# M715.net
KiCad netlist of a schematic drawn in EAGLE
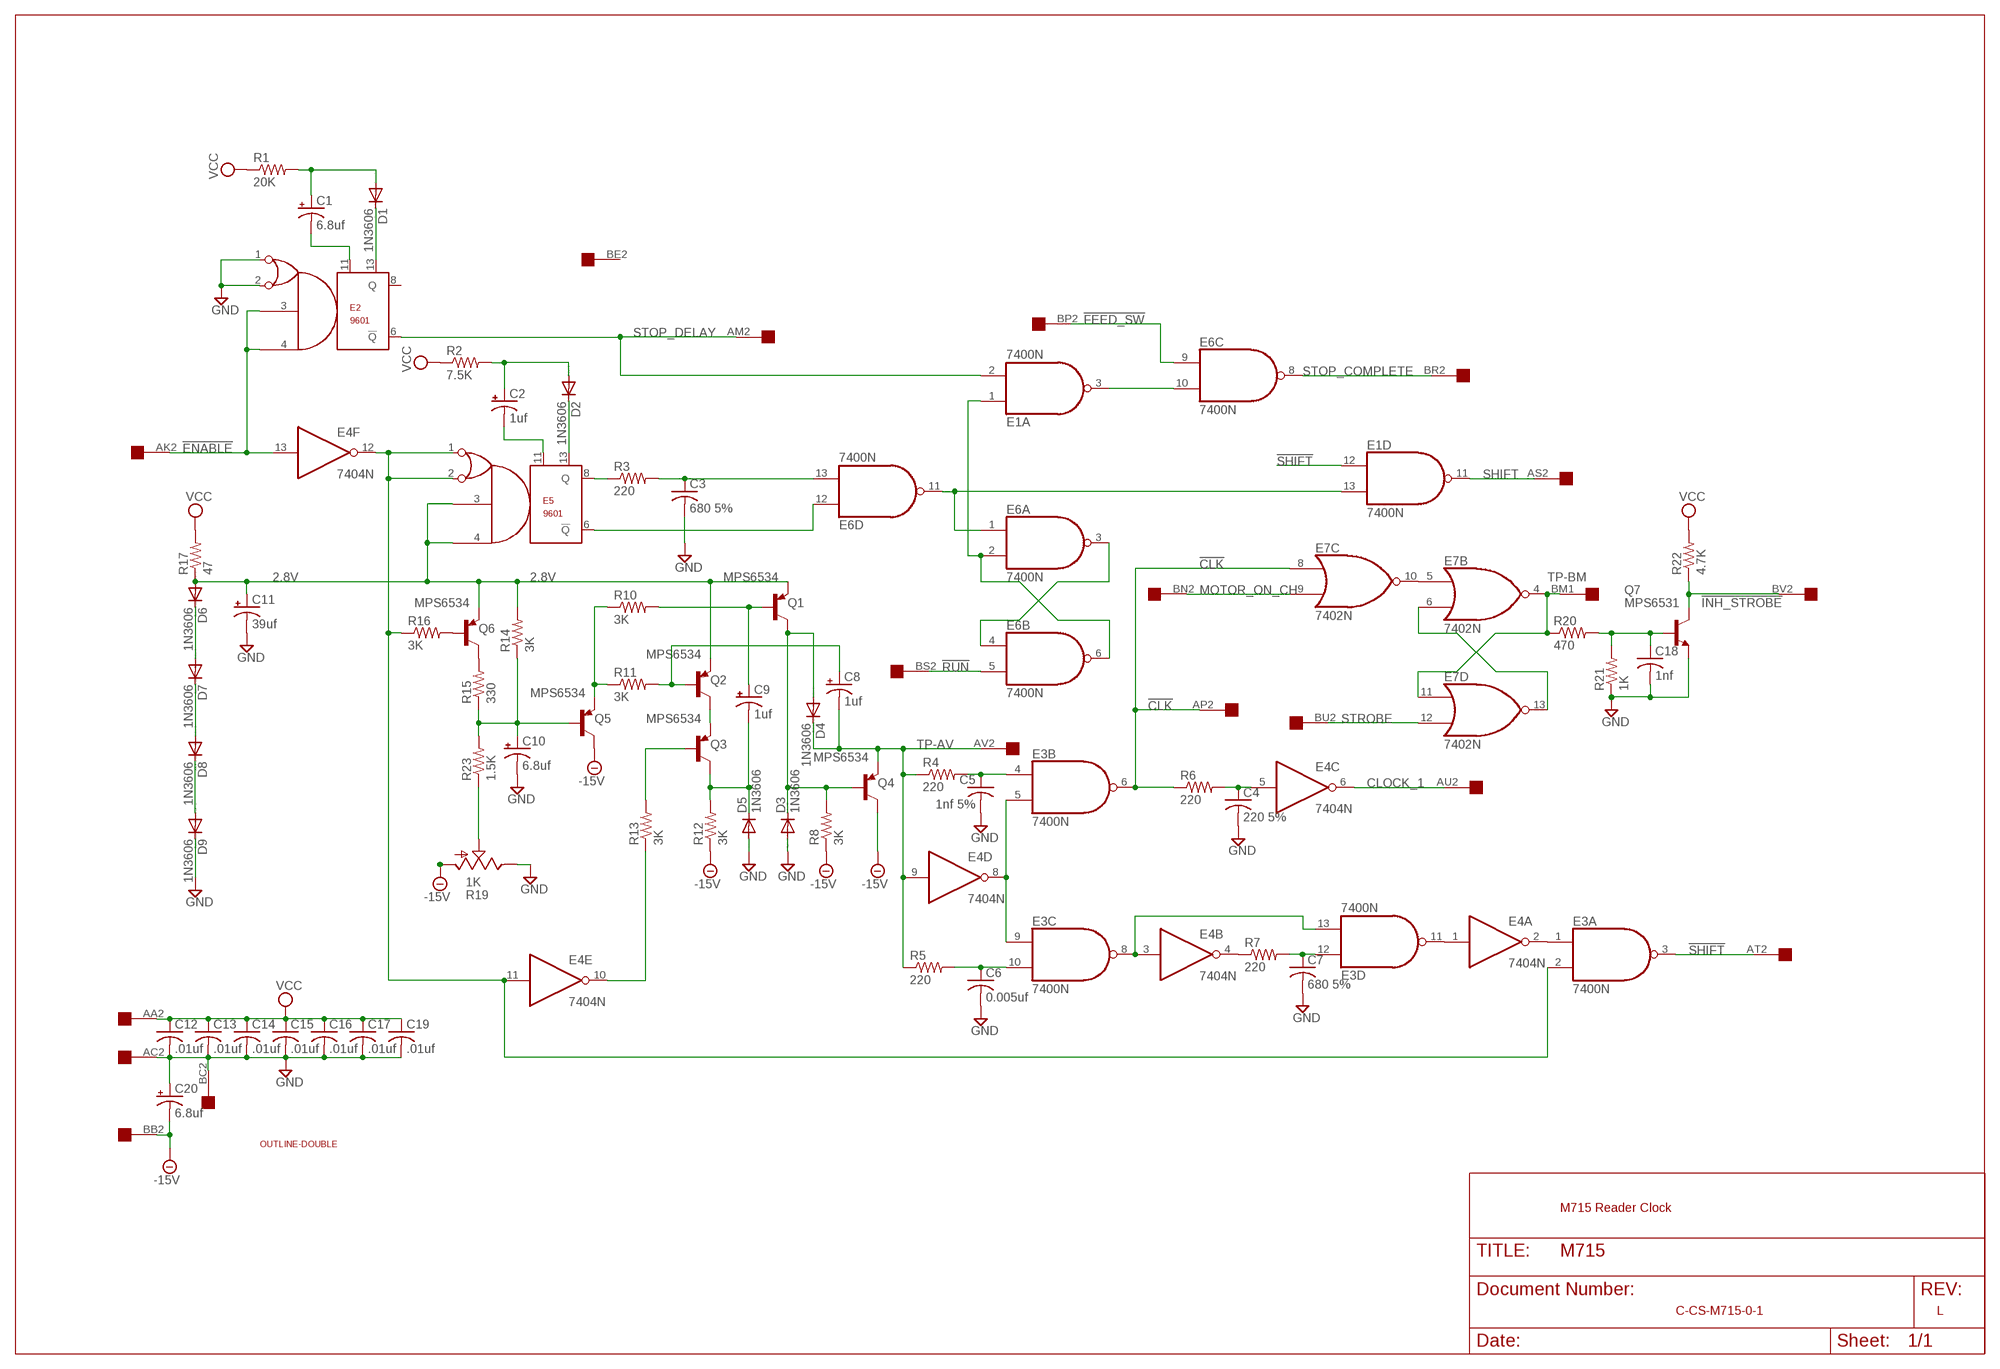
[diagram p0: schematic, sheet 1]

(export (version "E")
  (design (tool "Eeschema 10.0.6"))
  (components
    (comp (ref "C1")
      (value "6.8uf")
      (footprint "eagle-import:E22-6")
      (libsource (lib "eagle-import") (part "CPOL-USE22-6AXIAL"))
    )
    (comp (ref "C2")
      (value "1uf")
      (footprint "eagle-import:E15-5")
      (libsource (lib "eagle-import") (part "CPOL-USE15-5AXIAL"))
    )
    (comp (ref "C3")
      (value "680 5%")
      (footprint "eagle-import:C050-025X075")
      (libsource (lib "eagle-import") (part "C-US050-025X075"))
    )
    (comp (ref "C4")
      (value "220 5%")
      (footprint "eagle-import:C050-025X075")
      (libsource (lib "eagle-import") (part "C-US050-025X075"))
    )
    (comp (ref "C5")
      (value "1nf 5%")
      (footprint "eagle-import:C050-025X075")
      (libsource (lib "eagle-import") (part "C-US050-025X075"))
    )
    (comp (ref "C6")
      (value "0.005uf")
      (footprint "eagle-import:C050-025X075")
      (libsource (lib "eagle-import") (part "C-US050-025X075"))
    )
    (comp (ref "C7")
      (value "680 5%")
      (footprint "eagle-import:C050-025X075")
      (libsource (lib "eagle-import") (part "C-US050-025X075"))
    )
    (comp (ref "C8")
      (value "1uf")
      (footprint "eagle-import:E15-5")
      (libsource (lib "eagle-import") (part "CPOL-USE15-5AXIAL"))
    )
    (comp (ref "C9")
      (value "1uf")
      (footprint "eagle-import:E15-5")
      (libsource (lib "eagle-import") (part "CPOL-USE15-5AXIAL"))
    )
    (comp (ref "C10")
      (value "6.8uf")
      (footprint "eagle-import:E22-6")
      (libsource (lib "eagle-import") (part "CPOL-USE22-6AXIAL"))
    )
    (comp (ref "C11")
      (value "39uf")
      (footprint "eagle-import:E22-6")
      (libsource (lib "eagle-import") (part "CPOL-USE22-6AXIAL"))
    )
    (comp (ref "C12")
      (value ".01uf")
      (footprint "eagle-import:C050-025X075")
      (libsource (lib "eagle-import") (part "C-US050-025X075"))
    )
    (comp (ref "C13")
      (value ".01uf")
      (footprint "eagle-import:C050-025X075")
      (libsource (lib "eagle-import") (part "C-US050-025X075"))
    )
    (comp (ref "C14")
      (value ".01uf")
      (footprint "eagle-import:C050-025X075")
      (libsource (lib "eagle-import") (part "C-US050-025X075"))
    )
    (comp (ref "C15")
      (value ".01uf")
      (footprint "eagle-import:C050-025X075")
      (libsource (lib "eagle-import") (part "C-US050-025X075"))
    )
    (comp (ref "C16")
      (value ".01uf")
      (footprint "eagle-import:C050-025X075")
      (libsource (lib "eagle-import") (part "C-US050-025X075"))
    )
    (comp (ref "C17")
      (value ".01uf")
      (footprint "eagle-import:C050-025X075")
      (libsource (lib "eagle-import") (part "C-US050-025X075"))
    )
    (comp (ref "C18")
      (value "1nf")
      (footprint "eagle-import:C050-025X075")
      (libsource (lib "eagle-import") (part "C-US050-025X075"))
    )
    (comp (ref "C19")
      (value ".01uf")
      (footprint "eagle-import:C050-025X075")
      (libsource (lib "eagle-import") (part "C-US050-025X075"))
    )
    (comp (ref "C20")
      (value "6.8uf")
      (footprint "eagle-import:E22-6")
      (libsource (lib "eagle-import") (part "CPOL-USE22-6AXIAL"))
    )
    (comp (ref "D1")
      (value "1N3606")
      (footprint "eagle-import:DO35-10")
      (libsource (lib "eagle-import") (part "1N4148DO35-10"))
    )
    (comp (ref "D2")
      (value "1N3606")
      (footprint "eagle-import:DO35-10")
      (libsource (lib "eagle-import") (part "1N4148DO35-10"))
    )
    (comp (ref "D3")
      (value "1N3606")
      (footprint "eagle-import:DO35-10")
      (libsource (lib "eagle-import") (part "1N4148DO35-10"))
    )
    (comp (ref "D4")
      (value "1N3606")
      (footprint "eagle-import:DO35-10")
      (libsource (lib "eagle-import") (part "1N4148DO35-10"))
    )
    (comp (ref "D5")
      (value "1N3606")
      (footprint "eagle-import:DO35-10")
      (libsource (lib "eagle-import") (part "1N4148DO35-10"))
    )
    (comp (ref "D6")
      (value "1N3606")
      (footprint "eagle-import:DO35-10")
      (libsource (lib "eagle-import") (part "1N4148DO35-10"))
    )
    (comp (ref "D7")
      (value "1N3606")
      (footprint "eagle-import:DO35-10")
      (libsource (lib "eagle-import") (part "1N4148DO35-10"))
    )
    (comp (ref "D8")
      (value "1N3606")
      (footprint "eagle-import:DO35-10")
      (libsource (lib "eagle-import") (part "1N4148DO35-10"))
    )
    (comp (ref "D9")
      (value "1N3606")
      (footprint "eagle-import:DO35-10")
      (libsource (lib "eagle-import") (part "1N4148DO35-10"))
    )
    (comp (ref "E1")
      (value "7400N")
      (footprint "eagle-import:DIL14")
      (libsource (lib "eagle-import") (part "7400N"))
    )
    (comp (ref "E2")
      (value "9601")
      (footprint "eagle-import:DIL14")
      (libsource (lib "eagle-import") (part "9601"))
    )
    (comp (ref "E3")
      (value "7400N")
      (footprint "eagle-import:DIL14")
      (libsource (lib "eagle-import") (part "7400N"))
    )
    (comp (ref "E4")
      (value "7404N")
      (footprint "eagle-import:DIL14")
      (libsource (lib "eagle-import") (part "7404N"))
    )
    (comp (ref "E5")
      (value "9601")
      (footprint "eagle-import:DIL14")
      (libsource (lib "eagle-import") (part "9601"))
    )
    (comp (ref "E6")
      (value "7400N")
      (footprint "eagle-import:DIL14")
      (libsource (lib "eagle-import") (part "7400N"))
    )
    (comp (ref "E7")
      (value "7402N")
      (footprint "eagle-import:DIL14")
      (libsource (lib "eagle-import") (part "7402N"))
    )
    (comp (ref "Q1")
      (value "MPS6534")
      (footprint "eagle-import:TO92")
      (libsource (lib "eagle-import") (part "-PNP-TO92"))
    )
    (comp (ref "Q2")
      (value "MPS6534")
      (footprint "eagle-import:TO92")
      (libsource (lib "eagle-import") (part "-PNP-TO92"))
    )
    (comp (ref "Q3")
      (value "MPS6534")
      (footprint "eagle-import:TO92")
      (libsource (lib "eagle-import") (part "-PNP-TO92"))
    )
    (comp (ref "Q4")
      (value "MPS6534")
      (footprint "eagle-import:TO92")
      (libsource (lib "eagle-import") (part "-PNP-TO92"))
    )
    (comp (ref "Q5")
      (value "MPS6534")
      (footprint "eagle-import:TO92")
      (libsource (lib "eagle-import") (part "-PNP-TO92"))
    )
    (comp (ref "Q6")
      (value "MPS6534")
      (footprint "eagle-import:TO92")
      (libsource (lib "eagle-import") (part "-PNP-TO92"))
    )
    (comp (ref "Q7")
      (value "MPS6531")
      (footprint "eagle-import:TO92")
      (libsource (lib "eagle-import") (part "-NPN-TO92"))
    )
    (comp (ref "R1")
      (value "20K")
      (footprint "eagle-import:0207_10")
      (libsource (lib "eagle-import") (part "R-US_0207/10"))
    )
    (comp (ref "R2")
      (value "7.5K")
      (footprint "eagle-import:0207_10")
      (libsource (lib "eagle-import") (part "R-US_0207/10"))
    )
    (comp (ref "R3")
      (value "220")
      (footprint "eagle-import:0207_10")
      (libsource (lib "eagle-import") (part "R-US_0207/10"))
    )
    (comp (ref "R4")
      (value "220")
      (footprint "eagle-import:0207_10")
      (libsource (lib "eagle-import") (part "R-US_0207/10"))
    )
    (comp (ref "R5")
      (value "220")
      (footprint "eagle-import:0207_10")
      (libsource (lib "eagle-import") (part "R-US_0207/10"))
    )
    (comp (ref "R6")
      (value "220")
      (footprint "eagle-import:0207_10")
      (libsource (lib "eagle-import") (part "R-US_0207/10"))
    )
    (comp (ref "R7")
      (value "220")
      (footprint "eagle-import:0207_10")
      (libsource (lib "eagle-import") (part "R-US_0207/10"))
    )
    (comp (ref "R8")
      (value "3K")
      (footprint "eagle-import:0207_10")
      (libsource (lib "eagle-import") (part "R-US_0207/10"))
    )
    (comp (ref "R10")
      (value "3K")
      (footprint "eagle-import:0207_10")
      (libsource (lib "eagle-import") (part "R-US_0207/10"))
    )
    (comp (ref "R11")
      (value "3K")
      (footprint "eagle-import:0207_10")
      (libsource (lib "eagle-import") (part "R-US_0207/10"))
    )
    (comp (ref "R12")
      (value "3K")
      (footprint "eagle-import:0207_10")
      (libsource (lib "eagle-import") (part "R-US_0207/10"))
    )
    (comp (ref "R13")
      (value "3K")
      (footprint "eagle-import:0207_10")
      (libsource (lib "eagle-import") (part "R-US_0207/10"))
    )
    (comp (ref "R14")
      (value "3K")
      (footprint "eagle-import:0207_10")
      (libsource (lib "eagle-import") (part "R-US_0207/10"))
    )
    (comp (ref "R15")
      (value "330")
      (footprint "eagle-import:0207_10")
      (libsource (lib "eagle-import") (part "R-US_0207/10"))
    )
    (comp (ref "R16")
      (value "3K")
      (footprint "eagle-import:0207_10")
      (libsource (lib "eagle-import") (part "R-US_0207/10"))
    )
    (comp (ref "R17")
      (value "47")
      (footprint "eagle-import:0207_10")
      (libsource (lib "eagle-import") (part "R-US_0207/10"))
    )
    (comp (ref "R19")
      (value "1K")
      (footprint "eagle-import:PT-SPIN")
      (libsource (lib "eagle-import") (part "TRIM_US-PTSPIN"))
    )
    (comp (ref "R20")
      (value "470")
      (footprint "eagle-import:0207_10")
      (libsource (lib "eagle-import") (part "R-US_0207/10"))
    )
    (comp (ref "R21")
      (value "1K")
      (footprint "eagle-import:0207_10")
      (libsource (lib "eagle-import") (part "R-US_0207/10"))
    )
    (comp (ref "R22")
      (value "4.7K")
      (footprint "eagle-import:0207_10")
      (libsource (lib "eagle-import") (part "R-US_0207/10"))
    )
    (comp (ref "R23")
      (value "1.5K")
      (footprint "eagle-import:0207_10")
      (libsource (lib "eagle-import") (part "R-US_0207/10"))
    )
    (comp (ref "U$1")
      (value "DOUBLE")
      (footprint "eagle-import:EDGE-CON4")
      (libsource (lib "eagle-import") (part "DOUBLE"))
    )
    (comp (ref "U$2")
      (value "OUTLINE-DOUBLE")
      (footprint "eagle-import:DOUBLE")
      (libsource (lib "eagle-import") (part "OUTLINE-DOUBLE"))
    )
  )
  (nets
    (net (code "1") (name "-15V") (class "Default")
      (node (ref "C20") (pin "-") (pinfunction "-_-") (pintype "passive"))
      (node (ref "Q4") (pin "3") (pinfunction "C_3") (pintype "passive"))
      (node (ref "Q5") (pin "3") (pinfunction "C_3") (pintype "passive"))
      (node (ref "R12") (pin "1") (pinfunction "1_1") (pintype "passive"))
      (node (ref "R19") (pin "A") (pinfunction "A_A") (pintype "passive"))
      (node (ref "R8") (pin "1") (pinfunction "1_1") (pintype "passive"))
      (node (ref "U$1") (pin "BB2") (pinfunction "1_BB2") (pintype "bidirectional"))
    )
    (net (code "2") (name "/2.8V") (class "Default")
      (node (ref "C11") (pin "+") (pinfunction "+_+") (pintype "passive"))
      (node (ref "D6") (pin "A") (pinfunction "A_A") (pintype "passive"))
      (node (ref "E5") (pin "3") (pinfunction "P$3_3") (pintype "input"))
      (node (ref "E5") (pin "4") (pinfunction "P$4_4") (pintype "input"))
      (node (ref "Q1") (pin "1") (pinfunction "E_1") (pintype "passive"))
      (node (ref "Q2") (pin "1") (pinfunction "E_1") (pintype "passive"))
      (node (ref "Q6") (pin "1") (pinfunction "E_1") (pintype "passive"))
      (node (ref "R14") (pin "2") (pinfunction "2_2") (pintype "passive"))
      (node (ref "R17") (pin "1") (pinfunction "1_1") (pintype "passive"))
    )
    (net (code "3") (name "/CLOCK_1") (class "Default")
      (node (ref "E4") (pin "6") (pinfunction "O_6") (pintype "output"))
      (node (ref "U$1") (pin "AU2") (pinfunction "1_AU2") (pintype "bidirectional"))
    )
    (net (code "4") (name "/MOTOR_ON_CH") (class "Default")
      (node (ref "E7") (pin "9") (pinfunction "I1_9") (pintype "input"))
      (node (ref "U$1") (pin "BN2") (pinfunction "1_BN2") (pintype "bidirectional"))
    )
    (net (code "5") (name "/SHIFT") (class "Default")
      (node (ref "E1") (pin "11") (pinfunction "O_11") (pintype "output"))
      (node (ref "U$1") (pin "AS2") (pinfunction "1_AS2") (pintype "bidirectional"))
    )
    (net (code "6") (name "/STOP_COMPLETE") (class "Default")
      (node (ref "E6") (pin "8") (pinfunction "O_8") (pintype "output"))
      (node (ref "U$1") (pin "BR2") (pinfunction "1_BR2") (pintype "bidirectional"))
    )
    (net (code "7") (name "/STOP_DELAY") (class "Default")
      (node (ref "E1") (pin "2") (pinfunction "I1_2") (pintype "input"))
      (node (ref "E2") (pin "6") (pinfunction "~{Q}_6") (pintype "output"))
      (node (ref "U$1") (pin "AM2") (pinfunction "1_AM2") (pintype "bidirectional"))
    )
    (net (code "8") (name "/STROBE") (class "Default")
      (node (ref "E7") (pin "12") (pinfunction "I1_12") (pintype "input"))
      (node (ref "U$1") (pin "BU2") (pinfunction "1_BU2") (pintype "bidirectional"))
    )
    (net (code "9") (name "/TP-AV") (class "Default")
      (node (ref "C8") (pin "-") (pinfunction "-_-") (pintype "passive"))
      (node (ref "D4") (pin "C") (pinfunction "C_C") (pintype "passive"))
      (node (ref "E4") (pin "9") (pinfunction "I_9") (pintype "input"))
      (node (ref "Q4") (pin "1") (pinfunction "E_1") (pintype "passive"))
      (node (ref "R4") (pin "1") (pinfunction "1_1") (pintype "passive"))
      (node (ref "R5") (pin "1") (pinfunction "1_1") (pintype "passive"))
      (node (ref "U$1") (pin "AV2") (pinfunction "1_AV2") (pintype "bidirectional"))
    )
    (net (code "10") (name "/TP-BM") (class "Default")
      (node (ref "E7") (pin "11") (pinfunction "I0_11") (pintype "input"))
      (node (ref "E7") (pin "4") (pinfunction "O_4") (pintype "output"))
      (node (ref "R20") (pin "1") (pinfunction "1_1") (pintype "passive"))
      (node (ref "U$1") (pin "BM1") (pinfunction "1_BM1") (pintype "bidirectional"))
    )
    (net (code "11") (name "/~{CLK}") (class "Default")
      (node (ref "E3") (pin "6") (pinfunction "O_6") (pintype "output"))
      (node (ref "E7") (pin "8") (pinfunction "I0_8") (pintype "input"))
      (node (ref "R6") (pin "1") (pinfunction "1_1") (pintype "passive"))
      (node (ref "U$1") (pin "AP2") (pinfunction "1_AP2") (pintype "bidirectional"))
    )
    (net (code "12") (name "/~{ENABLE}") (class "Default")
      (node (ref "E2") (pin "3") (pinfunction "P$3_3") (pintype "input"))
      (node (ref "E2") (pin "4") (pinfunction "P$4_4") (pintype "input"))
      (node (ref "E4") (pin "13") (pinfunction "I_13") (pintype "input"))
      (node (ref "U$1") (pin "AK2") (pinfunction "1_AK2") (pintype "bidirectional"))
    )
    (net (code "13") (name "/~{FEED_SW}") (class "Default")
      (node (ref "E6") (pin "9") (pinfunction "I0_9") (pintype "input"))
      (node (ref "U$1") (pin "BP2") (pinfunction "1_BP2") (pintype "bidirectional"))
    )
    (net (code "14") (name "/~{INH_STROBE}") (class "Default")
      (node (ref "Q7") (pin "3") (pinfunction "C_3") (pintype "passive"))
      (node (ref "R22") (pin "1") (pinfunction "1_1") (pintype "passive"))
      (node (ref "U$1") (pin "BV2") (pinfunction "1_BV2") (pintype "bidirectional"))
    )
    (net (code "15") (name "/~{RUN}") (class "Default")
      (node (ref "E6") (pin "5") (pinfunction "I1_5") (pintype "input"))
      (node (ref "U$1") (pin "BS2") (pinfunction "1_BS2") (pintype "bidirectional"))
    )
    (net (code "16") (name "/~{SHIFT}") (class "Default")
      (node (ref "E1") (pin "12") (pinfunction "I0_12") (pintype "input"))
      (node (ref "E3") (pin "3") (pinfunction "O_3") (pintype "output"))
      (node (ref "U$1") (pin "AT2") (pinfunction "1_AT2") (pintype "bidirectional"))
    )
    (net (code "17") (name "GND") (class "Default")
      (node (ref "C10") (pin "-") (pinfunction "-_-") (pintype "passive"))
      (node (ref "C11") (pin "-") (pinfunction "-_-") (pintype "passive"))
      (node (ref "C12") (pin "2") (pinfunction "2_2") (pintype "passive"))
      (node (ref "C13") (pin "2") (pinfunction "2_2") (pintype "passive"))
      (node (ref "C14") (pin "2") (pinfunction "2_2") (pintype "passive"))
      (node (ref "C15") (pin "2") (pinfunction "2_2") (pintype "passive"))
      (node (ref "C16") (pin "2") (pinfunction "2_2") (pintype "passive"))
      (node (ref "C17") (pin "2") (pinfunction "2_2") (pintype "passive"))
      (node (ref "C18") (pin "2") (pinfunction "2_2") (pintype "passive"))
      (node (ref "C19") (pin "2") (pinfunction "2_2") (pintype "passive"))
      (node (ref "C20") (pin "+") (pinfunction "+_+") (pintype "passive"))
      (node (ref "C3") (pin "2") (pinfunction "2_2") (pintype "passive"))
      (node (ref "C4") (pin "2") (pinfunction "2_2") (pintype "passive"))
      (node (ref "C5") (pin "2") (pinfunction "2_2") (pintype "passive"))
      (node (ref "C6") (pin "2") (pinfunction "2_2") (pintype "passive"))
      (node (ref "C7") (pin "2") (pinfunction "2_2") (pintype "passive"))
      (node (ref "D3") (pin "A") (pinfunction "A_A") (pintype "passive"))
      (node (ref "D5") (pin "A") (pinfunction "A_A") (pintype "passive"))
      (node (ref "D9") (pin "C") (pinfunction "C_C") (pintype "passive"))
      (node (ref "E2") (pin "1") (pinfunction "P$1_1") (pintype "input"))
      (node (ref "E2") (pin "2") (pinfunction "P$2_2") (pintype "input"))
      (node (ref "Q7") (pin "1") (pinfunction "E_1") (pintype "passive"))
      (node (ref "R19") (pin "E") (pinfunction "E_E") (pintype "passive"))
      (node (ref "R21") (pin "1") (pinfunction "1_1") (pintype "passive"))
      (node (ref "U$1") (pin "AC2") (pinfunction "1_AC2") (pintype "bidirectional"))
      (node (ref "U$1") (pin "BC2") (pinfunction "1_BC2") (pintype "bidirectional"))
    )
    (net (code "18") (name "Net-(C1-Pad+)") (class "Default")
      (node (ref "C1") (pin "+") (pinfunction "+_+") (pintype "passive"))
      (node (ref "D1") (pin "A") (pinfunction "A_A") (pintype "passive"))
      (node (ref "R1") (pin "2") (pinfunction "2_2") (pintype "passive"))
    )
    (net (code "19") (name "Net-(C2-Pad+)") (class "Default")
      (node (ref "C2") (pin "+") (pinfunction "+_+") (pintype "passive"))
      (node (ref "D2") (pin "A") (pinfunction "A_A") (pintype "passive"))
      (node (ref "R2") (pin "2") (pinfunction "2_2") (pintype "passive"))
    )
    (net (code "20") (name "Net-(D6-PadC)") (class "Default")
      (node (ref "D6") (pin "C") (pinfunction "C_C") (pintype "passive"))
      (node (ref "D7") (pin "A") (pinfunction "A_A") (pintype "passive"))
    )
    (net (code "21") (name "Net-(D7-PadC)") (class "Default")
      (node (ref "D7") (pin "C") (pinfunction "C_C") (pintype "passive"))
      (node (ref "D8") (pin "A") (pinfunction "A_A") (pintype "passive"))
    )
    (net (code "22") (name "Net-(D8-PadC)") (class "Default")
      (node (ref "D8") (pin "C") (pinfunction "C_C") (pintype "passive"))
      (node (ref "D9") (pin "A") (pinfunction "A_A") (pintype "passive"))
    )
    (net (code "23") (name "Net-(E1A-I0)") (class "Default")
      (node (ref "E1") (pin "1") (pinfunction "I0_1") (pintype "input"))
      (node (ref "E6") (pin "2") (pinfunction "I1_2") (pintype "input"))
      (node (ref "E6") (pin "6") (pinfunction "O_6") (pintype "output"))
    )
    (net (code "24") (name "Net-(E1A-O)") (class "Default")
      (node (ref "E1") (pin "3") (pinfunction "O_3") (pintype "output"))
      (node (ref "E6") (pin "10") (pinfunction "I1_10") (pintype "input"))
    )
    (net (code "25") (name "Net-(E1D-I1)") (class "Default")
      (node (ref "E1") (pin "13") (pinfunction "I1_13") (pintype "input"))
      (node (ref "E6") (pin "1") (pinfunction "I0_1") (pintype "input"))
      (node (ref "E6") (pin "11") (pinfunction "O_11") (pintype "output"))
    )
    (net (code "26") (name "Net-(E2A-P$5)") (class "Default")
      (node (ref "C1") (pin "-") (pinfunction "-_-") (pintype "passive"))
      (node (ref "E2") (pin "11") (pinfunction "P$5_11") (pintype "bidirectional"))
    )
    (net (code "27") (name "Net-(E2A-P$6)") (class "Default")
      (node (ref "D1") (pin "C") (pinfunction "C_C") (pintype "passive"))
      (node (ref "E2") (pin "13") (pinfunction "P$6_13") (pintype "bidirectional"))
    )
    (net (code "28") (name "Net-(E3A-I0)") (class "Default")
      (node (ref "E3") (pin "1") (pinfunction "I0_1") (pintype "input"))
      (node (ref "E4") (pin "2") (pinfunction "O_2") (pintype "output"))
    )
    (net (code "29") (name "Net-(E3A-I1)") (class "Default")
      (node (ref "E3") (pin "2") (pinfunction "I1_2") (pintype "input"))
      (node (ref "E4") (pin "11") (pinfunction "I_11") (pintype "input"))
      (node (ref "E4") (pin "12") (pinfunction "O_12") (pintype "output"))
      (node (ref "E5") (pin "1") (pinfunction "P$1_1") (pintype "input"))
      (node (ref "E5") (pin "2") (pinfunction "P$2_2") (pintype "input"))
      (node (ref "R16") (pin "1") (pinfunction "1_1") (pintype "passive"))
    )
    (net (code "30") (name "Net-(E3B-I0)") (class "Default")
      (node (ref "C5") (pin "1") (pinfunction "1_1") (pintype "passive"))
      (node (ref "E3") (pin "4") (pinfunction "I0_4") (pintype "input"))
      (node (ref "R4") (pin "2") (pinfunction "2_2") (pintype "passive"))
    )
    (net (code "31") (name "Net-(E3B-I1)") (class "Default")
      (node (ref "E3") (pin "5") (pinfunction "I1_5") (pintype "input"))
      (node (ref "E3") (pin "9") (pinfunction "I0_9") (pintype "input"))
      (node (ref "E4") (pin "8") (pinfunction "O_8") (pintype "output"))
    )
    (net (code "32") (name "Net-(E3C-I1)") (class "Default")
      (node (ref "C6") (pin "1") (pinfunction "1_1") (pintype "passive"))
      (node (ref "E3") (pin "10") (pinfunction "I1_10") (pintype "input"))
      (node (ref "R5") (pin "2") (pinfunction "2_2") (pintype "passive"))
    )
    (net (code "33") (name "Net-(E3C-O)") (class "Default")
      (node (ref "E3") (pin "13") (pinfunction "I1_13") (pintype "input"))
      (node (ref "E3") (pin "8") (pinfunction "O_8") (pintype "output"))
      (node (ref "E4") (pin "3") (pinfunction "I_3") (pintype "input"))
    )
    (net (code "34") (name "Net-(E3D-I0)") (class "Default")
      (node (ref "C7") (pin "1") (pinfunction "1_1") (pintype "passive"))
      (node (ref "E3") (pin "12") (pinfunction "I0_12") (pintype "input"))
      (node (ref "R7") (pin "2") (pinfunction "2_2") (pintype "passive"))
    )
    (net (code "35") (name "Net-(E3D-O)") (class "Default")
      (node (ref "E3") (pin "11") (pinfunction "O_11") (pintype "output"))
      (node (ref "E4") (pin "1") (pinfunction "I_1") (pintype "input"))
    )
    (net (code "36") (name "Net-(E4B-O)") (class "Default")
      (node (ref "E4") (pin "4") (pinfunction "O_4") (pintype "output"))
      (node (ref "R7") (pin "1") (pinfunction "1_1") (pintype "passive"))
    )
    (net (code "37") (name "Net-(E4C-I)") (class "Default")
      (node (ref "C4") (pin "1") (pinfunction "1_1") (pintype "passive"))
      (node (ref "E4") (pin "5") (pinfunction "I_5") (pintype "input"))
      (node (ref "R6") (pin "2") (pinfunction "2_2") (pintype "passive"))
    )
    (net (code "38") (name "Net-(E4E-O)") (class "Default")
      (node (ref "E4") (pin "10") (pinfunction "O_10") (pintype "output"))
      (node (ref "R13") (pin "1") (pinfunction "1_1") (pintype "passive"))
    )
    (net (code "39") (name "Net-(E5A-P$5)") (class "Default")
      (node (ref "C2") (pin "-") (pinfunction "-_-") (pintype "passive"))
      (node (ref "E5") (pin "11") (pinfunction "P$5_11") (pintype "bidirectional"))
    )
    (net (code "40") (name "Net-(E5A-P$6)") (class "Default")
      (node (ref "D2") (pin "C") (pinfunction "C_C") (pintype "passive"))
      (node (ref "E5") (pin "13") (pinfunction "P$6_13") (pintype "bidirectional"))
    )
    (net (code "41") (name "Net-(E5A-Q)") (class "Default")
      (node (ref "E5") (pin "8") (pinfunction "Q_8") (pintype "output"))
      (node (ref "R3") (pin "1") (pinfunction "1_1") (pintype "passive"))
    )
    (net (code "42") (name "Net-(E5A-~{Q})") (class "Default")
      (node (ref "E5") (pin "6") (pinfunction "~{Q}_6") (pintype "output"))
      (node (ref "E6") (pin "12") (pinfunction "I0_12") (pintype "input"))
    )
    (net (code "43") (name "Net-(E6A-O)") (class "Default")
      (node (ref "E6") (pin "3") (pinfunction "O_3") (pintype "output"))
      (node (ref "E6") (pin "4") (pinfunction "I0_4") (pintype "input"))
    )
    (net (code "44") (name "Net-(E6D-I1)") (class "Default")
      (node (ref "C3") (pin "1") (pinfunction "1_1") (pintype "passive"))
      (node (ref "E6") (pin "13") (pinfunction "I1_13") (pintype "input"))
      (node (ref "R3") (pin "2") (pinfunction "2_2") (pintype "passive"))
    )
    (net (code "45") (name "Net-(E7B-I0)") (class "Default")
      (node (ref "E7") (pin "10") (pinfunction "O_10") (pintype "output"))
      (node (ref "E7") (pin "5") (pinfunction "I0_5") (pintype "input"))
    )
    (net (code "46") (name "Net-(E7B-I1)") (class "Default")
      (node (ref "E7") (pin "13") (pinfunction "O_13") (pintype "output"))
      (node (ref "E7") (pin "6") (pinfunction "I1_6") (pintype "input"))
    )
    (net (code "47") (name "Net-(Q1-B)") (class "Default")
      (node (ref "C9") (pin "+") (pinfunction "+_+") (pintype "passive"))
      (node (ref "Q1") (pin "2") (pinfunction "B_2") (pintype "passive"))
      (node (ref "R10") (pin "2") (pinfunction "2_2") (pintype "passive"))
    )
    (net (code "48") (name "Net-(Q1-C)") (class "Default")
      (node (ref "D3") (pin "C") (pinfunction "C_C") (pintype "passive"))
      (node (ref "D4") (pin "A") (pinfunction "A_A") (pintype "passive"))
      (node (ref "Q1") (pin "3") (pinfunction "C_3") (pintype "passive"))
      (node (ref "Q4") (pin "2") (pinfunction "B_2") (pintype "passive"))
      (node (ref "R8") (pin "2") (pinfunction "2_2") (pintype "passive"))
    )
    (net (code "49") (name "Net-(Q2-B)") (class "Default")
      (node (ref "C8") (pin "+") (pinfunction "+_+") (pintype "passive"))
      (node (ref "Q2") (pin "2") (pinfunction "B_2") (pintype "passive"))
      (node (ref "R11") (pin "2") (pinfunction "2_2") (pintype "passive"))
    )
    (net (code "50") (name "Net-(Q2-C)") (class "Default")
      (node (ref "Q2") (pin "3") (pinfunction "C_3") (pintype "passive"))
      (node (ref "Q3") (pin "1") (pinfunction "E_1") (pintype "passive"))
    )
    (net (code "51") (name "Net-(Q3-B)") (class "Default")
      (node (ref "Q3") (pin "2") (pinfunction "B_2") (pintype "passive"))
      (node (ref "R13") (pin "2") (pinfunction "2_2") (pintype "passive"))
    )
    (net (code "52") (name "Net-(Q3-C)") (class "Default")
      (node (ref "C9") (pin "-") (pinfunction "-_-") (pintype "passive"))
      (node (ref "D5") (pin "C") (pinfunction "C_C") (pintype "passive"))
      (node (ref "Q3") (pin "3") (pinfunction "C_3") (pintype "passive"))
      (node (ref "R12") (pin "2") (pinfunction "2_2") (pintype "passive"))
    )
    (net (code "53") (name "Net-(Q5-B)") (class "Default")
      (node (ref "C10") (pin "+") (pinfunction "+_+") (pintype "passive"))
      (node (ref "Q5") (pin "2") (pinfunction "B_2") (pintype "passive"))
      (node (ref "R14") (pin "1") (pinfunction "1_1") (pintype "passive"))
      (node (ref "R15") (pin "1") (pinfunction "1_1") (pintype "passive"))
      (node (ref "R23") (pin "2") (pinfunction "2_2") (pintype "passive"))
    )
    (net (code "54") (name "Net-(Q5-E)") (class "Default")
      (node (ref "Q5") (pin "1") (pinfunction "E_1") (pintype "passive"))
      (node (ref "R10") (pin "1") (pinfunction "1_1") (pintype "passive"))
      (node (ref "R11") (pin "1") (pinfunction "1_1") (pintype "passive"))
    )
    (net (code "55") (name "Net-(Q6-B)") (class "Default")
      (node (ref "Q6") (pin "2") (pinfunction "B_2") (pintype "passive"))
      (node (ref "R16") (pin "2") (pinfunction "2_2") (pintype "passive"))
    )
    (net (code "56") (name "Net-(Q6-C)") (class "Default")
      (node (ref "Q6") (pin "3") (pinfunction "C_3") (pintype "passive"))
      (node (ref "R15") (pin "2") (pinfunction "2_2") (pintype "passive"))
    )
    (net (code "57") (name "Net-(Q7-B)") (class "Default")
      (node (ref "C18") (pin "1") (pinfunction "1_1") (pintype "passive"))
      (node (ref "Q7") (pin "2") (pinfunction "B_2") (pintype "passive"))
      (node (ref "R20") (pin "2") (pinfunction "2_2") (pintype "passive"))
      (node (ref "R21") (pin "2") (pinfunction "2_2") (pintype "passive"))
    )
    (net (code "58") (name "Net-(R19-PadS)") (class "Default")
      (node (ref "R19") (pin "S") (pinfunction "S_S") (pintype "passive"))
      (node (ref "R23") (pin "1") (pinfunction "1_1") (pintype "passive"))
    )
    (net (code "59") (name "VCC") (class "Default")
      (node (ref "C12") (pin "1") (pinfunction "1_1") (pintype "passive"))
      (node (ref "C13") (pin "1") (pinfunction "1_1") (pintype "passive"))
      (node (ref "C14") (pin "1") (pinfunction "1_1") (pintype "passive"))
      (node (ref "C15") (pin "1") (pinfunction "1_1") (pintype "passive"))
      (node (ref "C16") (pin "1") (pinfunction "1_1") (pintype "passive"))
      (node (ref "C17") (pin "1") (pinfunction "1_1") (pintype "passive"))
      (node (ref "C19") (pin "1") (pinfunction "1_1") (pintype "passive"))
      (node (ref "R1") (pin "1") (pinfunction "1_1") (pintype "passive"))
      (node (ref "R17") (pin "2") (pinfunction "2_2") (pintype "passive"))
      (node (ref "R2") (pin "1") (pinfunction "1_1") (pintype "passive"))
      (node (ref "R22") (pin "2") (pinfunction "2_2") (pintype "passive"))
      (node (ref "U$1") (pin "AA2") (pinfunction "1_AA2") (pintype "bidirectional"))
    )
    (net (code "60") (name "unconnected-(E2A-Q-Pad8)") (class "Default")
      (node (ref "E2") (pin "8") (pinfunction "Q_8") (pintype "output"))
    )
    (net (code "61") (name "unconnected-(U$1AT-1-PadBE2)") (class "Default")
      (node (ref "U$1") (pin "BE2") (pinfunction "1_BE2") (pintype "bidirectional"))
    )
  )
)
